# powMan_powPath.net
KiCad netlist of a schematic drawn in Altium Designer
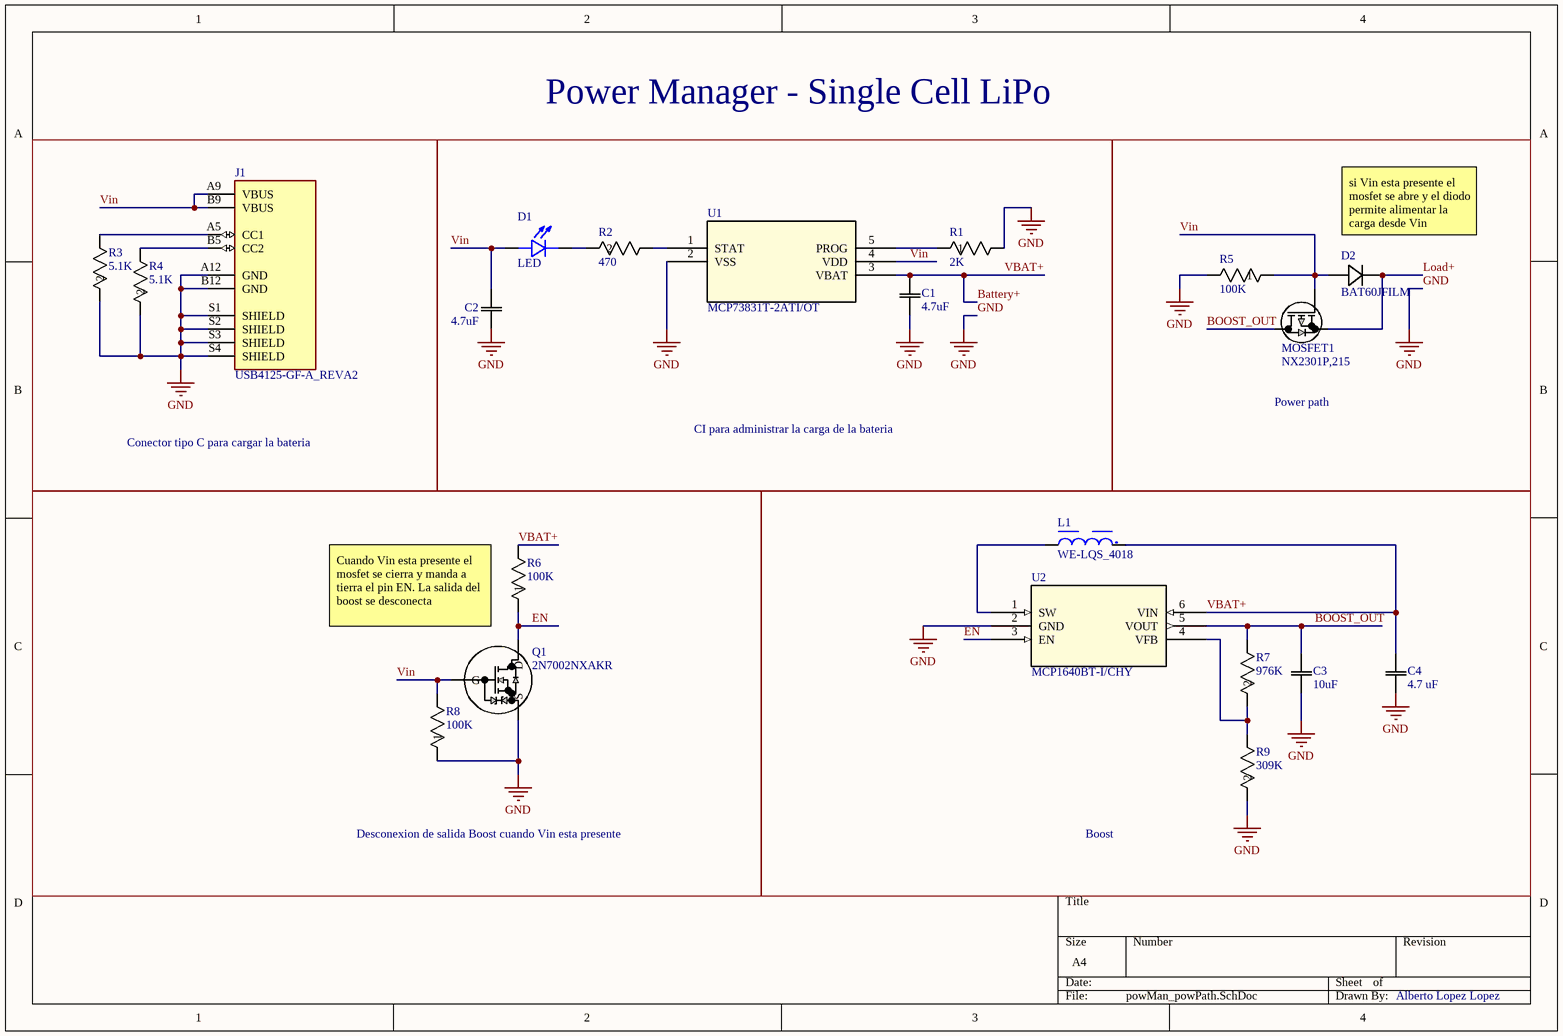
[diagram p0: powMan_powPath.SchDoc]

(export (version "E")
  (design (tool "Eeschema 10.0.6"))
  (components
    (comp (ref "C1")
      (value "4.7uF")
      (footprint "CAP_0603_CL10A_1P6XP8_SAM")
      (description "4.7 uF Capacitor 0603")
      (fields
        (field (name "MANUFACTURER_PART_NUMBER") "CL10A475KP8NNNC")
        (field (name "COPYRIGHT") "Copyright (C) 2025 Ultra Librarian. All rights reserved.")
      )
      (libsource (lib "myLib_Alberto") (part "CL10A475KP8NNNC"))
    )
    (comp (ref "C2")
      (value "4.7uF")
      (footprint "CAP_0603_CL10A_1P6XP8_SAM")
      (description "4.7 uF Capacitor 0603")
      (fields
        (field (name "MANUFACTURER_PART_NUMBER") "CL10A475KP8NNNC")
        (field (name "COPYRIGHT") "Copyright (C) 2025 Ultra Librarian. All rights reserved.")
      )
      (libsource (lib "myLib_Alberto") (part "CL10A475KP8NNNC"))
    )
    (comp (ref "C3")
      (value "10uF")
      (footprint "CAP_0603_X1_WAL")
      (description "capacitor 10 uF 0603")
      (fields
        (field (name "MANUFACTURER_PART_NUMBER") "0603X106M100CT")
        (field (name "COPYRIGHT") "Copyright (C) 2026 Ultra Librarian. All rights reserved.")
      )
      (libsource (lib "myLib_Alberto") (part "0603X106M100CT"))
    )
    (comp (ref "C4")
      (value "4.7 uF")
      (footprint "CAP_0603_CL10A_1P6XP8_SAM")
      (description "4.7 uF Capacitor 0603")
      (fields
        (field (name "MANUFACTURER_PART_NUMBER") "CL10A475KP8NNNC")
        (field (name "COPYRIGHT") "Copyright (C) 2025 Ultra Librarian. All rights reserved.")
      )
      (libsource (lib "myLib_Alberto") (part "CL10A475KP8NNNC"))
    )
    (comp (ref "D1")
      (value "LED")
      (footprint "LED_KT-0805W")
      (description "Light Emitting Diodes")
      (fields (field (name "MF") "Hubei KENTO Elec") (field (name "MP") "KT-0805W"))
      (libsource (lib "myLib_Alberto") (part "KT-0805W"))
    )
    (comp (ref "D2")
      (value "BAT60JFILM")
      (footprint "CR_60JFILM_STM")
      (description "10 V General pupose  Signal Schottky Diode")
      (fields (field (name "COPYRIGHT") "Copyright (C) 2025 Ultra Librarian. All rights reserved."))
      (libsource (lib "myLib_Alberto") (part "BAT60JFILM"))
    )
    (comp (ref "J1")
      (value "USB4125-GF-A_REVA2")
      (footprint "GCT_USB4125-GF-A_REVA2")
      (description "USB C female connector")
      (libsource (lib "myLib_Alberto") (part "USB4125-GF-A_REVA2"))
    )
    (comp (ref "L1")
      (value "WE-LQS_4018")
      (footprint "WE-LQS_4018")
      (description "INDICATEUR FIXE 4,7 UH 1,7 A 70 MOHM CMS")
      (fields (field (name "MF") "WÃ¼rth Elektronik") (field (name "MP") "74404042047"))
      (libsource (lib "myLib_Alberto") (part "WE-LQS_4018"))
    )
    (comp (ref "MOSFET1")
      (value "NX2301P,215")
      (footprint "SOT23_TO-236AB_NEX-L")
      (description "MOSFET P-Chanel 400mW")
      (fields (field (name "COPYRIGHT") "Copyright (C) 2025 Ultra Librarian. All rights reserved."))
      (libsource (lib "myLib_Alberto") (part "NX2301P,215"))
    )
    (comp (ref "Q1")
      (value "2N7002NXAKR")
      (footprint "TO-236AB_SOT23_NEX")
      (description "N-MOSFET 60VDS 190ID")
      (fields (field (name "COPYRIGHT") "Copyright (C) 2025 Ultra Librarian. All rights reserved."))
      (libsource (lib "myLib_Alberto") (part "2N7002NXAKR"))
    )
    (comp (ref "R1")
      (value "2K")
      (footprint "RC0603N_YAG-L")
      (description "RES SMD 2kO 1% 1/10W 0603")
      (fields
        (field (name "MANUFACTURER_PART_NUMBER") "RC0603FR-072KL")
        (field (name "COPYRIGHT") "Copyright (C) 2025 Ultra Librarian. All rights reserved.")
      )
      (libsource (lib "myLib_Alberto") (part "RC0603FR-072KL"))
    )
    (comp (ref "R2")
      (value "470")
      (footprint "RC0603N_YAG-L")
      (description "RESISTOR; 0603; 470 OHM; 1%; 100PPM; 0.1W; THICK FILM")
      (fields
        (field (name "MANUFACTURER_PART_NUMBER") "RC0603FR-07470RL")
        (field (name "COPYRIGHT") "Copyright (C) 2026 Ultra Librarian. All rights reserved.")
      )
      (libsource (lib "myLib_Alberto") (part "RC0603FR-07470RL"))
    )
    (comp (ref "R3")
      (value "5.1K")
      (footprint "RC0603N_YAG-L")
      (description "RES 5.1K SMD 0603")
      (fields
        (field (name "MANUFACTURER_PART_NUMBER") "RC0603FR-075K1L")
        (field (name "COPYRIGHT") "Copyright (C) 2025 Ultra Librarian. All rights reserved.")
      )
      (libsource (lib "myLib_Alberto") (part "RC0603FR-075K1L"))
    )
    (comp (ref "R4")
      (value "5.1K")
      (footprint "RC0603N_YAG-L")
      (description "RES 5.1K SMD 0603")
      (fields
        (field (name "MANUFACTURER_PART_NUMBER") "RC0603FR-075K1L")
        (field (name "COPYRIGHT") "Copyright (C) 2025 Ultra Librarian. All rights reserved.")
      )
      (libsource (lib "myLib_Alberto") (part "RC0603FR-075K1L"))
    )
    (comp (ref "R5")
      (value "100K")
      (footprint "RC0603N_YAG-L")
      (description "RES, 100 k, 1%, 0.1 W, 0603")
      (fields
        (field (name "MANUFACTURER_PART_NUMBER") "RC0603FR-07100KL")
        (field (name "COPYRIGHT") "Copyright (C) 2025 Ultra Librarian. All rights reserved.")
      )
      (libsource (lib "myLib_Alberto") (part "RC0603FR-07100KL"))
    )
    (comp (ref "R6")
      (value "100K")
      (footprint "RC0603N_YAG-L - duplicate")
      (description "RES, 100 k, 1%, 0.1 W, 0603")
      (fields
        (field (name "MANUFACTURER_PART_NUMBER") "RC0603FR-07100KL")
        (field (name "COPYRIGHT") "Copyright (C) 2025 Ultra Librarian. All rights reserved.")
      )
      (libsource (lib "myLib_Alberto") (part "RC0603FR-07100KL"))
    )
    (comp (ref "R7")
      (value "976K")
      (footprint "RC0603N_YAG")
      (description "resistor 976K 0603")
      (fields
        (field (name "MANUFACTURER_PART_NUMBER") "RC0603FR-07976KL")
        (field (name "COPYRIGHT") "Copyright (C) 2026 Ultra Librarian. All rights reserved.")
      )
      (libsource (lib "myLib_Alberto") (part "RC0603FR-07976KL"))
    )
    (comp (ref "R8")
      (value "100K")
      (footprint "RC0603N_YAG-L - duplicate")
      (description "RES, 100 k, 1%, 0.1 W, 0603")
      (fields
        (field (name "MANUFACTURER_PART_NUMBER") "RC0603FR-07100KL")
        (field (name "COPYRIGHT") "Copyright (C) 2025 Ultra Librarian. All rights reserved.")
      )
      (libsource (lib "myLib_Alberto") (part "RC0603FR-07100KL"))
    )
    (comp (ref "R9")
      (value "309K")
      (footprint "RC0603N_YAG")
      (description "resistor 309K 0603")
      (fields
        (field (name "MANUFACTURER_PART_NUMBER") "RC0603FR-07309KL")
        (field (name "COPYRIGHT") "Copyright (C) 2025 Ultra Librarian. All rights reserved.")
      )
      (libsource (lib "myLib_Alberto") (part "RC0603FR-07309KL"))
    )
    (comp (ref "U1")
      (value "MCP73831T-2ATI/OT")
      (footprint "SOT-23-5_MC_MCH")
      (description "Miniature Single-Cell, Fully Integrated Li-Ion,\r\nLi-Polymer Charge Management Controller")
      (fields (field (name "COPYRIGHT") "Copyright (C) 2026 Ultra Librarian. All rights reserved."))
      (libsource (lib "myLib_Alberto") (part "MCP73831T-2ATIOT"))
    )
    (comp (ref "U2")
      (value "MCP1640BT-I/CHY")
      (footprint "SOT-23-6_MC_MCH")
      (description "Boost Regulator max input 5.5V output 2 - 5.5V max output 350mA")
      (fields (field (name "COPYRIGHT") "Copyright (C) 2025 Ultra Librarian. All rights reserved."))
      (libsource (lib "myLib_Alberto") (part "MCP1640BT-ICHY"))
    )
  )
  (nets
    (net (code "1") (name "/BOOST_OUT") (class "Default")
      (node (ref "C3") (pin "2") (pinfunction "2_2") (pintype "passive"))
      (node (ref "MOSFET1") (pin "1") (pintype "passive"))
      (node (ref "R7") (pin "1") (pinfunction "1_1") (pintype "passive"))
      (node (ref "U2") (pin "5") (pinfunction "VOUT_5") (pintype "output"))
    )
    (net (code "2") (name "/Battery+") (class "Default")
      (node (ref "C1") (pin "2") (pinfunction "2_2") (pintype "passive"))
      (node (ref "C4") (pin "2") (pinfunction "2_2") (pintype "passive"))
      (node (ref "L1") (pin "2") (pinfunction "1_2") (pintype "passive"))
      (node (ref "R6") (pin "2") (pinfunction "2_2") (pintype "passive"))
      (node (ref "U1") (pin "3") (pinfunction "VBAT_3") (pintype "passive"))
      (node (ref "U2") (pin "6") (pinfunction "VIN_6") (pintype "input"))
    )
    (net (code "3") (name "/EN") (class "Default")
      (node (ref "Q1") (pin "3") (pinfunction "D_3") (pintype "passive"))
      (node (ref "R6") (pin "1") (pinfunction "1_1") (pintype "passive"))
      (node (ref "U2") (pin "3") (pinfunction "EN_3") (pintype "input"))
    )
    (net (code "4") (name "/Load+") (class "Default")
      (node (ref "D2") (pin "1") (pinfunction "1_1") (pintype "passive"))
      (node (ref "MOSFET1") (pin "2") (pintype "passive"))
    )
    (net (code "5") (name "/Vin") (class "Default")
      (node (ref "C2") (pin "2") (pinfunction "2_2") (pintype "passive"))
      (node (ref "D1") (pin "A") (pinfunction "A_A") (pintype "passive"))
      (node (ref "D2") (pin "2") (pinfunction "2_2") (pintype "passive"))
      (node (ref "J1") (pin "A9") (pinfunction "VBUS_A9") (pintype "power_in"))
      (node (ref "J1") (pin "B9") (pinfunction "VBUS_B9") (pintype "power_in"))
      (node (ref "MOSFET1") (pin "3") (pintype "passive"))
      (node (ref "Q1") (pin "1") (pinfunction "G_1") (pintype "passive"))
      (node (ref "R5") (pin "1") (pinfunction "1_1") (pintype "passive"))
      (node (ref "R8") (pin "2") (pinfunction "2_2") (pintype "passive"))
      (node (ref "U1") (pin "4") (pinfunction "VDD_4") (pintype "passive"))
    )
    (net (code "6") (name "GND") (class "Default")
      (node (ref "C1") (pin "1") (pinfunction "1_1") (pintype "passive"))
      (node (ref "C2") (pin "1") (pinfunction "1_1") (pintype "passive"))
      (node (ref "C3") (pin "1") (pinfunction "1_1") (pintype "passive"))
      (node (ref "C4") (pin "1") (pinfunction "1_1") (pintype "passive"))
      (node (ref "J1") (pin "A12") (pinfunction "GND_A12") (pintype "power_in"))
      (node (ref "J1") (pin "B12") (pinfunction "GND_B12") (pintype "power_in"))
      (node (ref "J1") (pin "S1") (pinfunction "SHIELD_S1") (pintype "passive"))
      (node (ref "J1") (pin "S2") (pinfunction "SHIELD_S2") (pintype "passive"))
      (node (ref "J1") (pin "S3") (pinfunction "SHIELD_S3") (pintype "passive"))
      (node (ref "J1") (pin "S4") (pinfunction "SHIELD_S4") (pintype "passive"))
      (node (ref "Q1") (pin "2") (pinfunction "S_2") (pintype "passive"))
      (node (ref "R1") (pin "2") (pinfunction "2_2") (pintype "passive"))
      (node (ref "R3") (pin "2") (pinfunction "2_2") (pintype "passive"))
      (node (ref "R4") (pin "2") (pinfunction "2_2") (pintype "passive"))
      (node (ref "R5") (pin "2") (pinfunction "2_2") (pintype "passive"))
      (node (ref "R8") (pin "1") (pinfunction "1_1") (pintype "passive"))
      (node (ref "R9") (pin "2") (pinfunction "2_2") (pintype "passive"))
      (node (ref "U1") (pin "2") (pinfunction "VSS_2") (pintype "passive"))
      (node (ref "U2") (pin "2") (pinfunction "GND_2") (pintype "power_in"))
    )
    (net (code "7") (name "Net-(D1-PadC)") (class "Default")
      (node (ref "D1") (pin "C") (pinfunction "C_C") (pintype "passive"))
      (node (ref "R2") (pin "2") (pinfunction "2_2") (pintype "passive"))
    )
    (net (code "8") (name "Net-(J1-CC1)") (class "Default")
      (node (ref "J1") (pin "A5") (pinfunction "CC1_A5") (pintype "bidirectional"))
      (node (ref "R3") (pin "1") (pinfunction "1_1") (pintype "passive"))
    )
    (net (code "9") (name "Net-(J1-CC2)") (class "Default")
      (node (ref "J1") (pin "B5") (pinfunction "CC2_B5") (pintype "bidirectional"))
      (node (ref "R4") (pin "1") (pinfunction "1_1") (pintype "passive"))
    )
    (net (code "10") (name "Net-(L1-2)") (class "Default")
      (node (ref "L1") (pin "1") (pinfunction "2_1") (pintype "passive"))
      (node (ref "U2") (pin "1") (pinfunction "SW_1") (pintype "input"))
    )
    (net (code "11") (name "Net-(U1-PROG)") (class "Default")
      (node (ref "R1") (pin "1") (pinfunction "1_1") (pintype "passive"))
      (node (ref "U1") (pin "5") (pinfunction "PROG_5") (pintype "passive"))
    )
    (net (code "12") (name "Net-(U1-STAT)") (class "Default")
      (node (ref "R2") (pin "1") (pinfunction "1_1") (pintype "passive"))
      (node (ref "U1") (pin "1") (pinfunction "STAT_1") (pintype "passive"))
    )
    (net (code "13") (name "Net-(U2-VFB)") (class "Default")
      (node (ref "R7") (pin "2") (pinfunction "2_2") (pintype "passive"))
      (node (ref "R9") (pin "1") (pinfunction "1_1") (pintype "passive"))
      (node (ref "U2") (pin "4") (pinfunction "VFB_4") (pintype "passive"))
    )
  )
)
